# Codeshelf-0009_v03.net
KiCad netlist of a schematic drawn in EAGLE
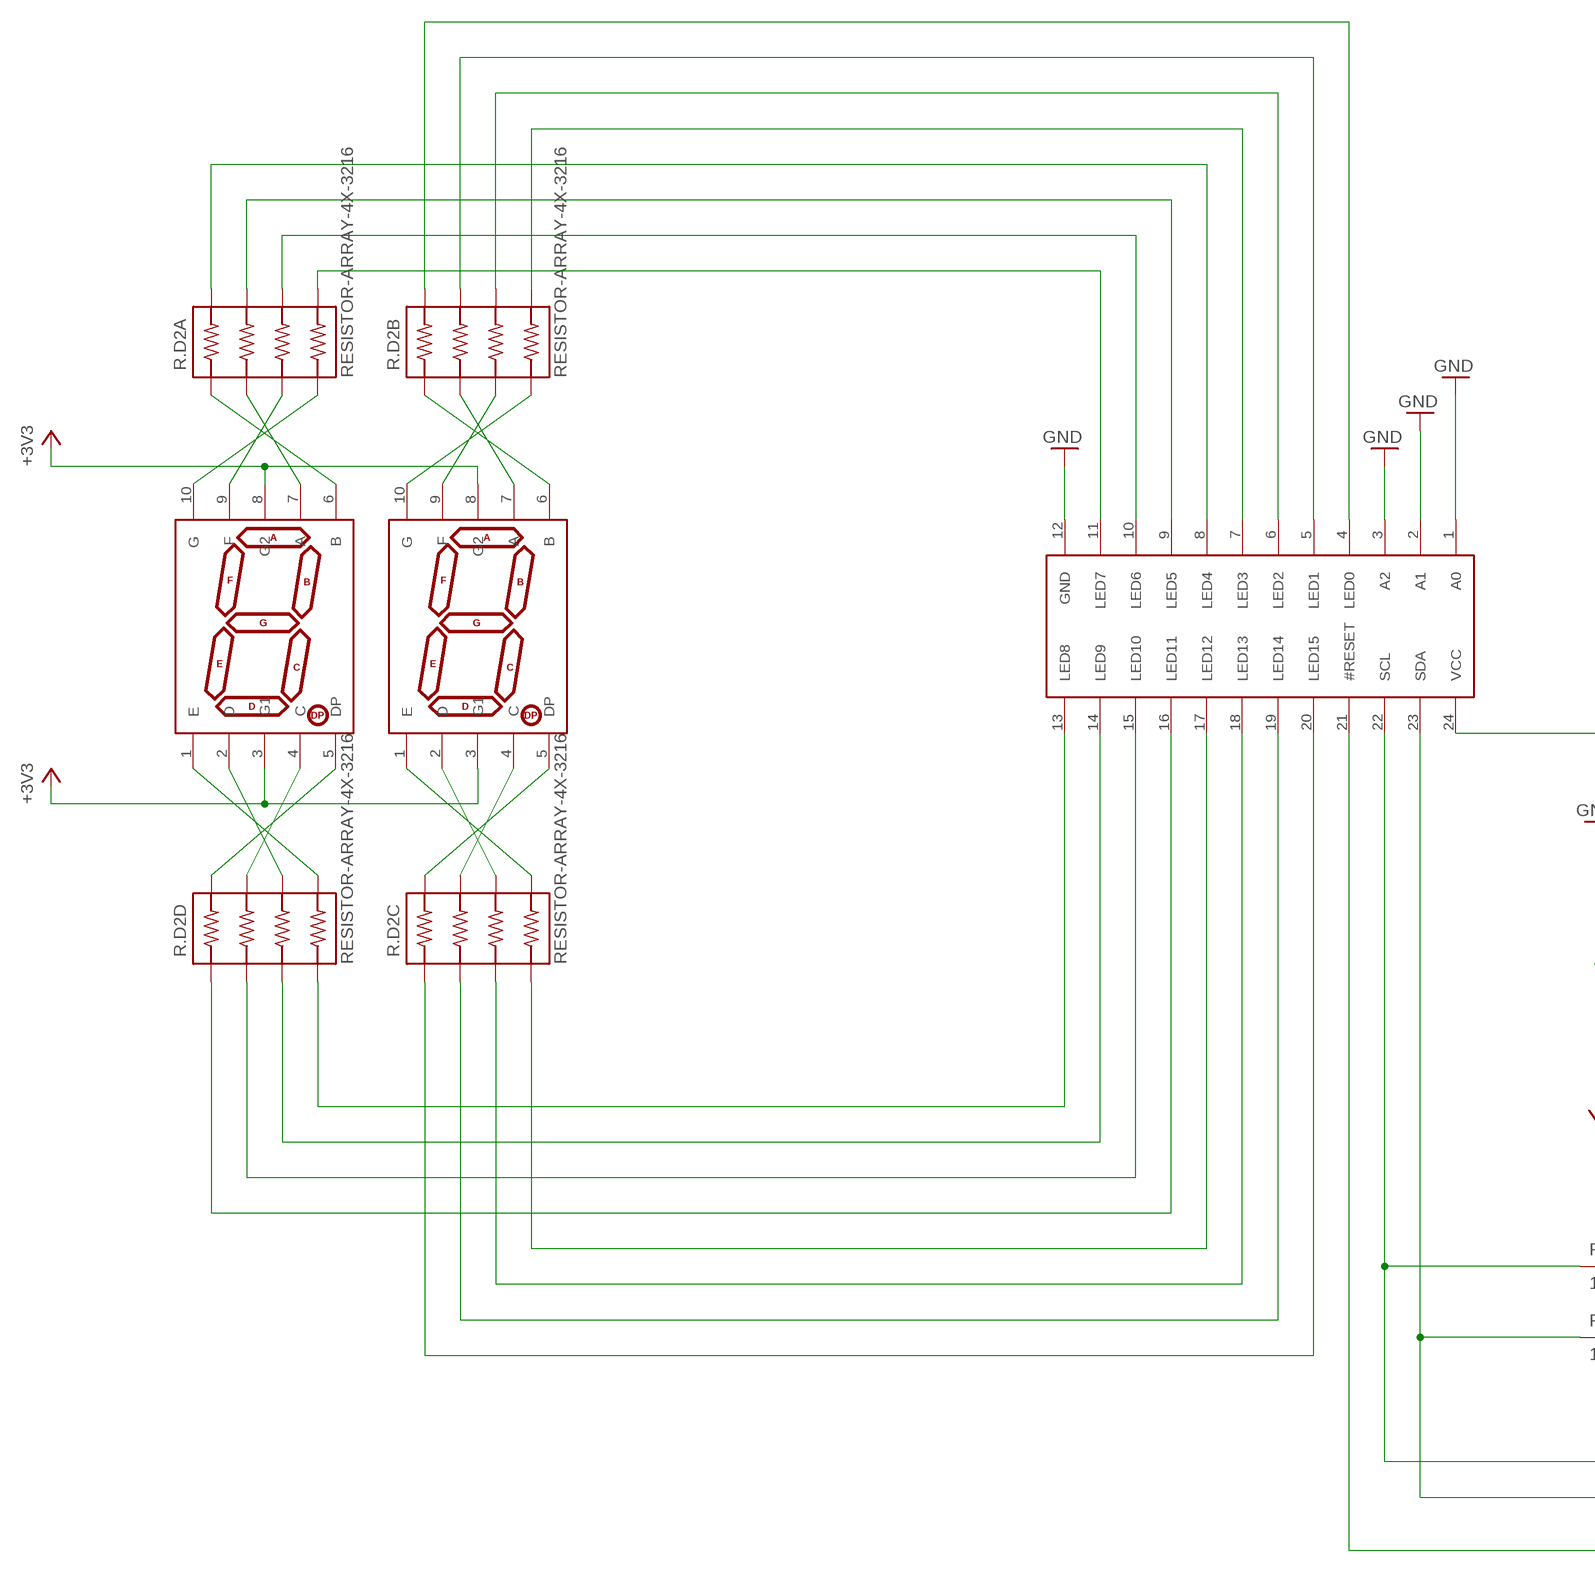
[diagram p0: schematic, sheet 1, part 1 of 2]
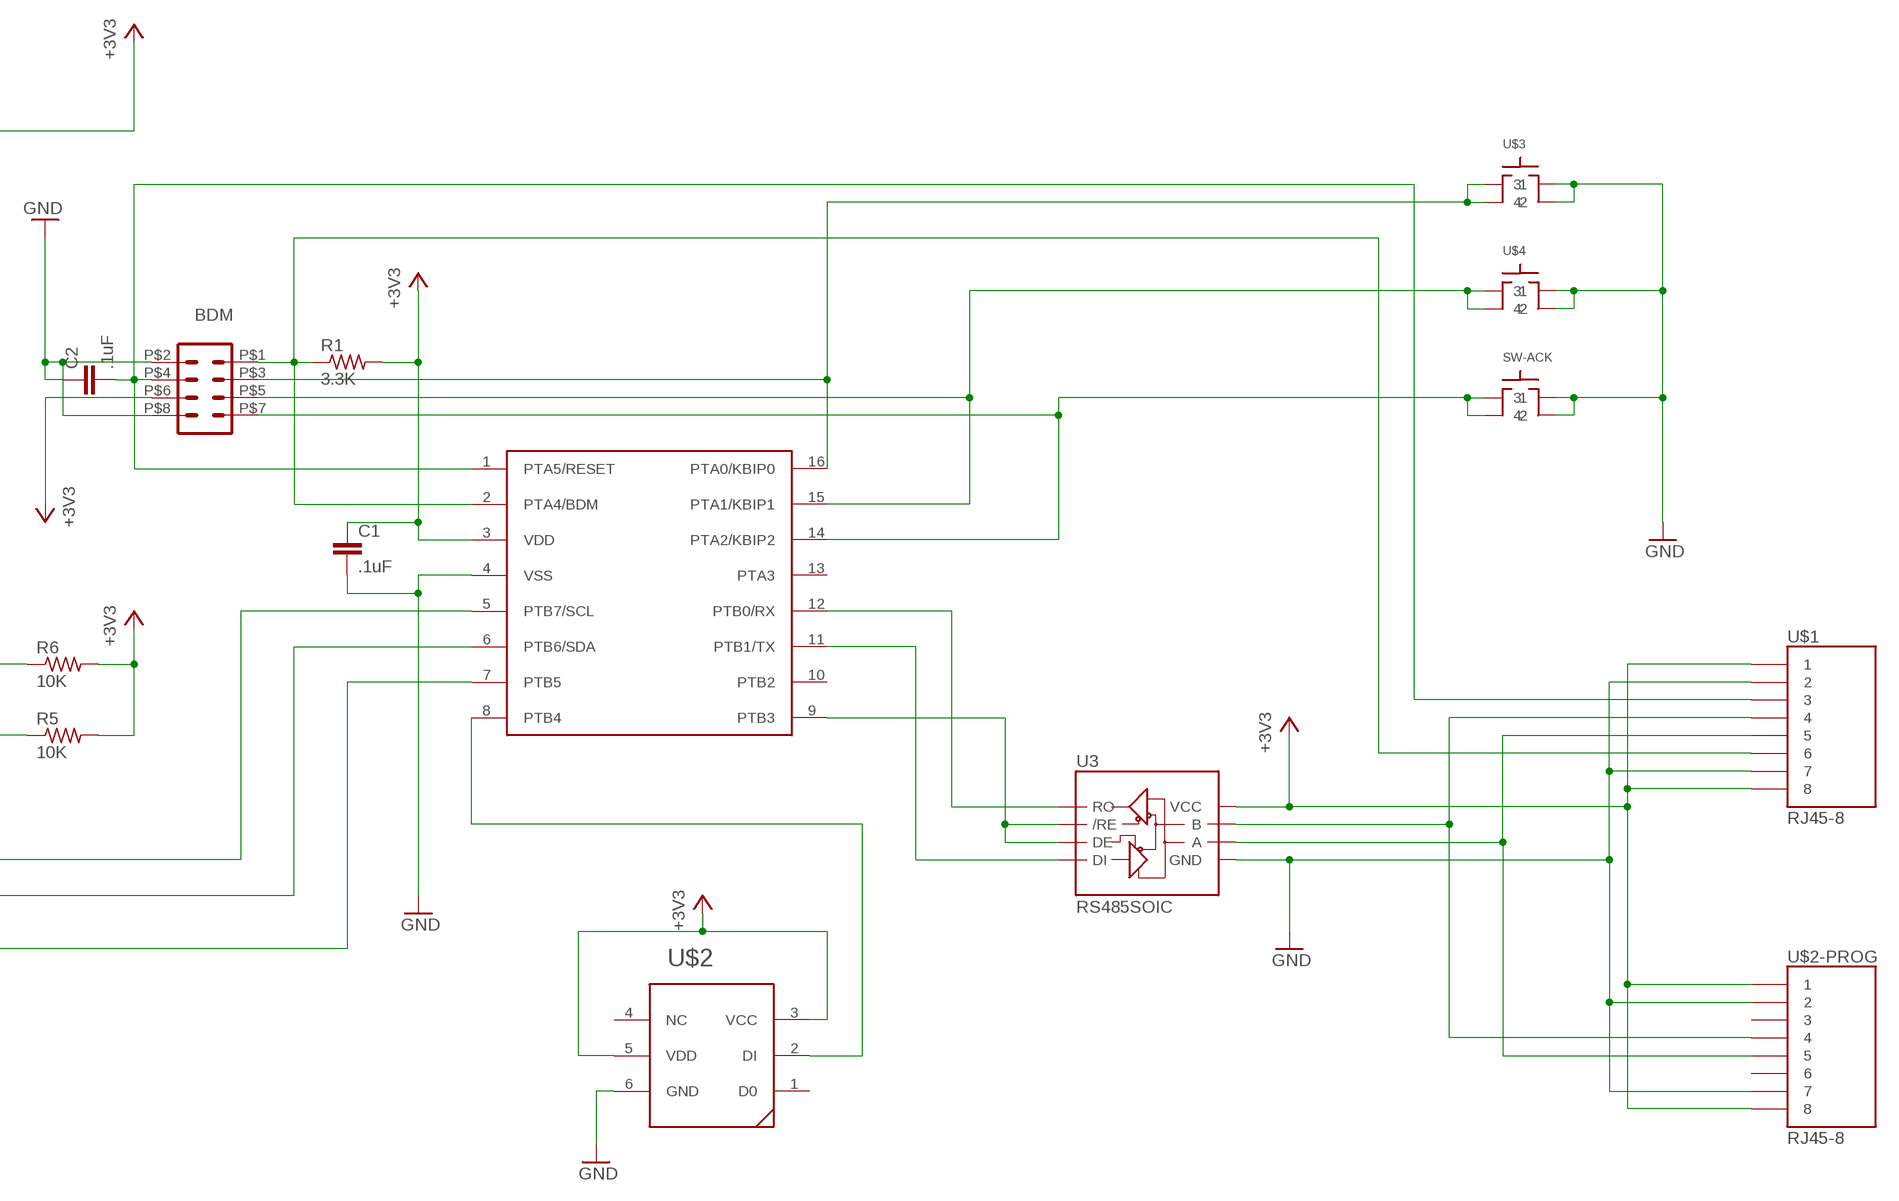
[diagram p1: schematic, sheet 1, part 2 of 2]

(export (version "E")
  (design (tool "Eeschema 10.0.6"))
  (components
    (comp (ref "BDM")
      (value "TP2X4SMD")
      (footprint "eagle-import:SMD4X2")
      (libsource (lib "eagle-import") (part "TP2X4SMD"))
    )
    (comp (ref "C1")
      (value ".1uF")
      (footprint "eagle-import:C0402")
      (libsource (lib "eagle-import") (part "RF-C0402"))
    )
    (comp (ref "C2")
      (value ".1uF")
      (footprint "eagle-import:C0402")
      (libsource (lib "eagle-import") (part "RF-C0402"))
    )
    (comp (ref "LED1")
      (value "7SEGMENT-1DIGITSMD")
      (footprint "eagle-import:7SEGMENT-1DIG-.40-SMD")
      (libsource (lib "eagle-import") (part "7SEGMENT-1DIGITSMD"))
    )
    (comp (ref "LED2")
      (value "7SEGMENT-1DIGITSMD")
      (footprint "eagle-import:7SEGMENT-1DIG-.40-SMD")
      (libsource (lib "eagle-import") (part "7SEGMENT-1DIGITSMD"))
    )
    (comp (ref "R.D2A")
      (value "RESISTOR-ARRAY-4X-3216")
      (footprint "eagle-import:3216-4X")
      (libsource (lib "eagle-import") (part "RESISTOR-ARRAY-4X-3216"))
    )
    (comp (ref "R.D2B")
      (value "RESISTOR-ARRAY-4X-3216")
      (footprint "eagle-import:3216-4X")
      (libsource (lib "eagle-import") (part "RESISTOR-ARRAY-4X-3216"))
    )
    (comp (ref "R.D2C")
      (value "RESISTOR-ARRAY-4X-3216")
      (footprint "eagle-import:3216-4X")
      (libsource (lib "eagle-import") (part "RESISTOR-ARRAY-4X-3216"))
    )
    (comp (ref "R.D2D")
      (value "RESISTOR-ARRAY-4X-3216")
      (footprint "eagle-import:3216-4X")
      (libsource (lib "eagle-import") (part "RESISTOR-ARRAY-4X-3216"))
    )
    (comp (ref "R1")
      (value "3.3K")
      (footprint "eagle-import:RF-R0402")
      (libsource (lib "eagle-import") (part "RF-R0402"))
    )
    (comp (ref "R5")
      (value "10K")
      (footprint "eagle-import:RF-R0402")
      (libsource (lib "eagle-import") (part "RF-R0402"))
    )
    (comp (ref "R6")
      (value "10K")
      (footprint "eagle-import:RF-R0402")
      (libsource (lib "eagle-import") (part "RF-R0402"))
    )
    (comp (ref "SW-ACK")
      (value "SWITCH-TACTILE-320.03E11")
      (footprint "eagle-import:SWITCH-TACTILE-320.03E11")
      (libsource (lib "eagle-import") (part "SWITCH-TACTILE-320.03E11"))
    )
    (comp (ref "U$1")
      (value "RJ45-8")
      (footprint "eagle-import:MOLEX-0955016649")
      (libsource (lib "eagle-import") (part "RJ45-8"))
    )
    (comp (ref "U$2")
      (value "WS2812")
      (footprint "eagle-import:PLCC-6")
      (libsource (lib "eagle-import") (part "WS2812"))
    )
    (comp (ref "U$2-PROG")
      (value "RJ45-8")
      (footprint "eagle-import:MOLEX-0955016649")
      (libsource (lib "eagle-import") (part "RJ45-8"))
    )
    (comp (ref "U$3")
      (value "SWITCH-TACTILE")
      (footprint "eagle-import:ESWITCH-TL3301PF")
      (libsource (lib "eagle-import") (part "SWITCH-TACTILE"))
    )
    (comp (ref "U$4")
      (value "SWITCH-TACTILE")
      (footprint "eagle-import:ESWITCH-TL3301PF")
      (libsource (lib "eagle-import") (part "SWITCH-TACTILE"))
    )
    (comp (ref "U1")
      (value "MC9S08QG-DT")
      (footprint "eagle-import:TSSOP16")
      (libsource (lib "eagle-import") (part "MC9S08QG-DT"))
    )
    (comp (ref "U3")
      (value "RS485SOIC")
      (footprint "eagle-import:SO08")
      (libsource (lib "eagle-import") (part "RS485SOIC"))
    )
    (comp (ref "U4")
      (value "CAT9552")
      (footprint "eagle-import:TSSOP24")
      (libsource (lib "eagle-import") (part "CAT9552"))
    )
  )
  (nets
    (net (code "1") (name "+3V3") (class "Default")
      (node (ref "BDM") (pin "P$6") (pinfunction "6_P$6") (pintype "passive"))
      (node (ref "C1") (pin "1") (pinfunction "1_1") (pintype "passive"))
      (node (ref "LED1") (pin "3") (pinfunction "G1_3") (pintype "bidirectional"))
      (node (ref "LED1") (pin "8") (pinfunction "G2_8") (pintype "bidirectional"))
      (node (ref "LED2") (pin "3") (pinfunction "G1_3") (pintype "bidirectional"))
      (node (ref "LED2") (pin "8") (pinfunction "G2_8") (pintype "bidirectional"))
      (node (ref "R1") (pin "2") (pinfunction "2_2") (pintype "passive"))
      (node (ref "R5") (pin "2") (pinfunction "2_2") (pintype "passive"))
      (node (ref "R6") (pin "2") (pinfunction "2_2") (pintype "passive"))
      (node (ref "U$1") (pin "P$1") (pinfunction "1_P$1") (pintype "bidirectional"))
      (node (ref "U$1") (pin "P$8") (pinfunction "8_P$8") (pintype "bidirectional"))
      (node (ref "U$2") (pin "3") (pinfunction "VCC_3") (pintype "bidirectional"))
      (node (ref "U$2") (pin "5") (pinfunction "VDD_5") (pintype "bidirectional"))
      (node (ref "U$2-PROG") (pin "P$1") (pinfunction "1_P$1") (pintype "bidirectional"))
      (node (ref "U$2-PROG") (pin "P$8") (pinfunction "8_P$8") (pintype "bidirectional"))
      (node (ref "U1") (pin "3") (pinfunction "VDD_3") (pintype "bidirectional"))
      (node (ref "U3") (pin "8") (pinfunction "VCC_8") (pintype "bidirectional"))
      (node (ref "U4") (pin "24") (pinfunction "VCC_24") (pintype "bidirectional"))
    )
    (net (code "2") (name "GND") (class "Default")
      (node (ref "BDM") (pin "P$2") (pinfunction "2_P$2") (pintype "passive"))
      (node (ref "BDM") (pin "P$8") (pinfunction "8_P$8") (pintype "passive"))
      (node (ref "C1") (pin "2") (pinfunction "2_2") (pintype "passive"))
      (node (ref "C2") (pin "1") (pinfunction "1_1") (pintype "passive"))
      (node (ref "SW-ACK") (pin "P$3") (pinfunction "3_P$3") (pintype "input"))
      (node (ref "SW-ACK") (pin "P$4") (pinfunction "4_P$4") (pintype "input"))
      (node (ref "U$1") (pin "P$2") (pinfunction "2_P$2") (pintype "bidirectional"))
      (node (ref "U$1") (pin "P$7") (pinfunction "7_P$7") (pintype "bidirectional"))
      (node (ref "U$2") (pin "6") (pinfunction "GND_6") (pintype "bidirectional"))
      (node (ref "U$2-PROG") (pin "P$2") (pinfunction "2_P$2") (pintype "bidirectional"))
      (node (ref "U$2-PROG") (pin "P$7") (pinfunction "7_P$7") (pintype "bidirectional"))
      (node (ref "U$3") (pin "3") (pinfunction "3_3") (pintype "input"))
      (node (ref "U$3") (pin "4") (pinfunction "4_4") (pintype "input"))
      (node (ref "U$4") (pin "3") (pinfunction "3_3") (pintype "input"))
      (node (ref "U$4") (pin "4") (pinfunction "4_4") (pintype "input"))
      (node (ref "U1") (pin "4") (pinfunction "VSS_4") (pintype "bidirectional"))
      (node (ref "U3") (pin "5") (pinfunction "GND_5") (pintype "bidirectional"))
      (node (ref "U4") (pin "1") (pinfunction "A0_1") (pintype "bidirectional"))
      (node (ref "U4") (pin "12") (pinfunction "GND_12") (pintype "bidirectional"))
      (node (ref "U4") (pin "2") (pinfunction "A1_2") (pintype "bidirectional"))
      (node (ref "U4") (pin "3") (pinfunction "A2_3") (pintype "bidirectional"))
    )
    (net (code "3") (name "Net-(BDM-1)") (class "Default")
      (node (ref "BDM") (pin "P$1") (pinfunction "1_P$1") (pintype "passive"))
      (node (ref "R1") (pin "1") (pinfunction "1_1") (pintype "passive"))
      (node (ref "U$1") (pin "P$6") (pinfunction "6_P$6") (pintype "bidirectional"))
      (node (ref "U1") (pin "2") (pinfunction "PTA4/BDM_2") (pintype "bidirectional"))
    )
    (net (code "4") (name "Net-(BDM-3)") (class "Default")
      (node (ref "BDM") (pin "P$3") (pinfunction "3_P$3") (pintype "passive"))
      (node (ref "U$3") (pin "1") (pinfunction "1_1") (pintype "input"))
      (node (ref "U$3") (pin "2") (pinfunction "2_2") (pintype "input"))
      (node (ref "U1") (pin "16") (pinfunction "PTA0/KBIP0_16") (pintype "bidirectional"))
    )
    (net (code "5") (name "Net-(BDM-4)") (class "Default")
      (node (ref "BDM") (pin "P$4") (pinfunction "4_P$4") (pintype "passive"))
      (node (ref "C2") (pin "2") (pinfunction "2_2") (pintype "passive"))
      (node (ref "U$1") (pin "P$3") (pinfunction "3_P$3") (pintype "bidirectional"))
      (node (ref "U1") (pin "1") (pinfunction "PTA5/RESET_1") (pintype "bidirectional"))
    )
    (net (code "6") (name "Net-(BDM-5)") (class "Default")
      (node (ref "BDM") (pin "P$5") (pinfunction "5_P$5") (pintype "passive"))
      (node (ref "U$4") (pin "1") (pinfunction "1_1") (pintype "input"))
      (node (ref "U$4") (pin "2") (pinfunction "2_2") (pintype "input"))
      (node (ref "U1") (pin "15") (pinfunction "PTA1/KBIP1_15") (pintype "bidirectional"))
    )
    (net (code "7") (name "Net-(BDM-7)") (class "Default")
      (node (ref "BDM") (pin "P$7") (pinfunction "7_P$7") (pintype "passive"))
      (node (ref "SW-ACK") (pin "P$1") (pinfunction "1_P$1") (pintype "input"))
      (node (ref "SW-ACK") (pin "P$2") (pinfunction "2_P$2") (pintype "input"))
      (node (ref "U1") (pin "14") (pinfunction "PTA2/KBIP2_14") (pintype "bidirectional"))
    )
    (net (code "8") (name "Net-(LED1-A)") (class "Default")
      (node (ref "LED1") (pin "7") (pinfunction "A_7") (pintype "bidirectional"))
      (node (ref "R.D2B") (pin "2") (pinfunction "2A_2") (pintype "passive"))
    )
    (net (code "9") (name "Net-(LED1-B)") (class "Default")
      (node (ref "LED1") (pin "6") (pinfunction "B_6") (pintype "bidirectional"))
      (node (ref "R.D2B") (pin "1") (pinfunction "1A_1") (pintype "passive"))
    )
    (net (code "10") (name "Net-(LED1-C)") (class "Default")
      (node (ref "LED1") (pin "4") (pinfunction "C_4") (pintype "bidirectional"))
      (node (ref "R.D2C") (pin "7") (pinfunction "2B_7") (pintype "passive"))
    )
    (net (code "11") (name "Net-(LED1-D)") (class "Default")
      (node (ref "LED1") (pin "2") (pinfunction "D_2") (pintype "bidirectional"))
      (node (ref "R.D2C") (pin "6") (pinfunction "3B_6") (pintype "passive"))
    )
    (net (code "12") (name "Net-(LED1-DP)") (class "Default")
      (node (ref "LED1") (pin "5") (pinfunction "DP_5") (pintype "bidirectional"))
      (node (ref "R.D2C") (pin "8") (pinfunction "1B_8") (pintype "passive"))
    )
    (net (code "13") (name "Net-(LED1-E)") (class "Default")
      (node (ref "LED1") (pin "1") (pinfunction "E_1") (pintype "bidirectional"))
      (node (ref "R.D2C") (pin "5") (pinfunction "4B_5") (pintype "passive"))
    )
    (net (code "14") (name "Net-(LED1-F)") (class "Default")
      (node (ref "LED1") (pin "9") (pinfunction "F_9") (pintype "bidirectional"))
      (node (ref "R.D2B") (pin "3") (pinfunction "3A_3") (pintype "passive"))
    )
    (net (code "15") (name "Net-(LED1-G)") (class "Default")
      (node (ref "LED1") (pin "10") (pinfunction "G_10") (pintype "bidirectional"))
      (node (ref "R.D2B") (pin "4") (pinfunction "4A_4") (pintype "passive"))
    )
    (net (code "16") (name "Net-(LED2-A)") (class "Default")
      (node (ref "LED2") (pin "7") (pinfunction "A_7") (pintype "bidirectional"))
      (node (ref "R.D2A") (pin "2") (pinfunction "2A_2") (pintype "passive"))
    )
    (net (code "17") (name "Net-(LED2-B)") (class "Default")
      (node (ref "LED2") (pin "6") (pinfunction "B_6") (pintype "bidirectional"))
      (node (ref "R.D2A") (pin "1") (pinfunction "1A_1") (pintype "passive"))
    )
    (net (code "18") (name "Net-(LED2-C)") (class "Default")
      (node (ref "LED2") (pin "4") (pinfunction "C_4") (pintype "bidirectional"))
      (node (ref "R.D2D") (pin "7") (pinfunction "2B_7") (pintype "passive"))
    )
    (net (code "19") (name "Net-(LED2-D)") (class "Default")
      (node (ref "LED2") (pin "2") (pinfunction "D_2") (pintype "bidirectional"))
      (node (ref "R.D2D") (pin "6") (pinfunction "3B_6") (pintype "passive"))
    )
    (net (code "20") (name "Net-(LED2-DP)") (class "Default")
      (node (ref "LED2") (pin "5") (pinfunction "DP_5") (pintype "bidirectional"))
      (node (ref "R.D2D") (pin "8") (pinfunction "1B_8") (pintype "passive"))
    )
    (net (code "21") (name "Net-(LED2-E)") (class "Default")
      (node (ref "LED2") (pin "1") (pinfunction "E_1") (pintype "bidirectional"))
      (node (ref "R.D2D") (pin "5") (pinfunction "4B_5") (pintype "passive"))
    )
    (net (code "22") (name "Net-(LED2-F)") (class "Default")
      (node (ref "LED2") (pin "9") (pinfunction "F_9") (pintype "bidirectional"))
      (node (ref "R.D2A") (pin "3") (pinfunction "3A_3") (pintype "passive"))
    )
    (net (code "23") (name "Net-(LED2-G)") (class "Default")
      (node (ref "LED2") (pin "10") (pinfunction "G_10") (pintype "bidirectional"))
      (node (ref "R.D2A") (pin "4") (pinfunction "4A_4") (pintype "passive"))
    )
    (net (code "24") (name "Net-(R.D2A-1B)") (class "Default")
      (node (ref "R.D2A") (pin "8") (pinfunction "1B_8") (pintype "passive"))
      (node (ref "U4") (pin "8") (pinfunction "LED4_8") (pintype "bidirectional"))
    )
    (net (code "25") (name "Net-(R.D2A-2B)") (class "Default")
      (node (ref "R.D2A") (pin "7") (pinfunction "2B_7") (pintype "passive"))
      (node (ref "U4") (pin "9") (pinfunction "LED5_9") (pintype "bidirectional"))
    )
    (net (code "26") (name "Net-(R.D2A-3B)") (class "Default")
      (node (ref "R.D2A") (pin "6") (pinfunction "3B_6") (pintype "passive"))
      (node (ref "U4") (pin "10") (pinfunction "LED6_10") (pintype "bidirectional"))
    )
    (net (code "27") (name "Net-(R.D2A-4B)") (class "Default")
      (node (ref "R.D2A") (pin "5") (pinfunction "4B_5") (pintype "passive"))
      (node (ref "U4") (pin "11") (pinfunction "LED7_11") (pintype "bidirectional"))
    )
    (net (code "28") (name "Net-(R.D2B-1B)") (class "Default")
      (node (ref "R.D2B") (pin "8") (pinfunction "1B_8") (pintype "passive"))
      (node (ref "U4") (pin "4") (pinfunction "LED0_4") (pintype "bidirectional"))
    )
    (net (code "29") (name "Net-(R.D2B-2B)") (class "Default")
      (node (ref "R.D2B") (pin "7") (pinfunction "2B_7") (pintype "passive"))
      (node (ref "U4") (pin "5") (pinfunction "LED1_5") (pintype "bidirectional"))
    )
    (net (code "30") (name "Net-(R.D2B-3B)") (class "Default")
      (node (ref "R.D2B") (pin "6") (pinfunction "3B_6") (pintype "passive"))
      (node (ref "U4") (pin "6") (pinfunction "LED2_6") (pintype "bidirectional"))
    )
    (net (code "31") (name "Net-(R.D2B-4B)") (class "Default")
      (node (ref "R.D2B") (pin "5") (pinfunction "4B_5") (pintype "passive"))
      (node (ref "U4") (pin "7") (pinfunction "LED3_7") (pintype "bidirectional"))
    )
    (net (code "32") (name "Net-(R.D2C-1A)") (class "Default")
      (node (ref "R.D2C") (pin "1") (pinfunction "1A_1") (pintype "passive"))
      (node (ref "U4") (pin "20") (pinfunction "LED15_20") (pintype "bidirectional"))
    )
    (net (code "33") (name "Net-(R.D2C-2A)") (class "Default")
      (node (ref "R.D2C") (pin "2") (pinfunction "2A_2") (pintype "passive"))
      (node (ref "U4") (pin "19") (pinfunction "LED14_19") (pintype "bidirectional"))
    )
    (net (code "34") (name "Net-(R.D2C-3A)") (class "Default")
      (node (ref "R.D2C") (pin "3") (pinfunction "3A_3") (pintype "passive"))
      (node (ref "U4") (pin "18") (pinfunction "LED13_18") (pintype "bidirectional"))
    )
    (net (code "35") (name "Net-(R.D2C-4A)") (class "Default")
      (node (ref "R.D2C") (pin "4") (pinfunction "4A_4") (pintype "passive"))
      (node (ref "U4") (pin "17") (pinfunction "LED12_17") (pintype "bidirectional"))
    )
    (net (code "36") (name "Net-(R.D2D-1A)") (class "Default")
      (node (ref "R.D2D") (pin "1") (pinfunction "1A_1") (pintype "passive"))
      (node (ref "U4") (pin "16") (pinfunction "LED11_16") (pintype "bidirectional"))
    )
    (net (code "37") (name "Net-(R.D2D-2A)") (class "Default")
      (node (ref "R.D2D") (pin "2") (pinfunction "2A_2") (pintype "passive"))
      (node (ref "U4") (pin "15") (pinfunction "LED10_15") (pintype "bidirectional"))
    )
    (net (code "38") (name "Net-(R.D2D-3A)") (class "Default")
      (node (ref "R.D2D") (pin "3") (pinfunction "3A_3") (pintype "passive"))
      (node (ref "U4") (pin "14") (pinfunction "LED9_14") (pintype "bidirectional"))
    )
    (net (code "39") (name "Net-(R.D2D-4A)") (class "Default")
      (node (ref "R.D2D") (pin "4") (pinfunction "4A_4") (pintype "passive"))
      (node (ref "U4") (pin "13") (pinfunction "LED8_13") (pintype "bidirectional"))
    )
    (net (code "40") (name "Net-(U$1-4)") (class "Default")
      (node (ref "U$1") (pin "P$4") (pinfunction "4_P$4") (pintype "bidirectional"))
      (node (ref "U$2-PROG") (pin "P$4") (pinfunction "4_P$4") (pintype "bidirectional"))
      (node (ref "U3") (pin "7") (pinfunction "B_7") (pintype "bidirectional"))
    )
    (net (code "41") (name "Net-(U$1-5)") (class "Default")
      (node (ref "U$1") (pin "P$5") (pinfunction "5_P$5") (pintype "bidirectional"))
      (node (ref "U$2-PROG") (pin "P$5") (pinfunction "5_P$5") (pintype "bidirectional"))
      (node (ref "U3") (pin "6") (pinfunction "A_6") (pintype "bidirectional"))
    )
    (net (code "42") (name "Net-(U$2-DI)") (class "Default")
      (node (ref "U$2") (pin "2") (pinfunction "DI_2") (pintype "bidirectional"))
      (node (ref "U1") (pin "8") (pinfunction "PTB4_8") (pintype "bidirectional"))
    )
    (net (code "43") (name "Net-(U1-PTB0{slash}RX)") (class "Default")
      (node (ref "U1") (pin "12") (pinfunction "PTB0/RX_12") (pintype "bidirectional"))
      (node (ref "U3") (pin "1") (pinfunction "RO_1") (pintype "bidirectional"))
    )
    (net (code "44") (name "Net-(U1-PTB1{slash}TX)") (class "Default")
      (node (ref "U1") (pin "11") (pinfunction "PTB1/TX_11") (pintype "bidirectional"))
      (node (ref "U3") (pin "4") (pinfunction "DI_4") (pintype "bidirectional"))
    )
    (net (code "45") (name "Net-(U1-PTB3)") (class "Default")
      (node (ref "U1") (pin "9") (pinfunction "PTB3_9") (pintype "bidirectional"))
      (node (ref "U3") (pin "2") (pinfunction "/RE_2") (pintype "bidirectional"))
      (node (ref "U3") (pin "3") (pinfunction "DE_3") (pintype "bidirectional"))
    )
    (net (code "46") (name "Net-(U1-PTB5)") (class "Default")
      (node (ref "U1") (pin "7") (pinfunction "PTB5_7") (pintype "bidirectional"))
      (node (ref "U4") (pin "21") (pinfunction "#RESET_21") (pintype "bidirectional"))
    )
    (net (code "47") (name "Net-(U1-PTB6{slash}SDA)") (class "Default")
      (node (ref "R5") (pin "1") (pinfunction "1_1") (pintype "passive"))
      (node (ref "U1") (pin "6") (pinfunction "PTB6/SDA_6") (pintype "bidirectional"))
      (node (ref "U4") (pin "23") (pinfunction "SDA_23") (pintype "bidirectional"))
    )
    (net (code "48") (name "Net-(U1-PTB7{slash}SCL)") (class "Default")
      (node (ref "R6") (pin "1") (pinfunction "1_1") (pintype "passive"))
      (node (ref "U1") (pin "5") (pinfunction "PTB7/SCL_5") (pintype "bidirectional"))
      (node (ref "U4") (pin "22") (pinfunction "SCL_22") (pintype "bidirectional"))
    )
    (net (code "49") (name "unconnected-(U$2-D0-Pad1)") (class "Default")
      (node (ref "U$2") (pin "1") (pinfunction "D0_1") (pintype "bidirectional"))
    )
    (net (code "50") (name "unconnected-(U$2-NC-Pad4)") (class "Default")
      (node (ref "U$2") (pin "4") (pinfunction "NC_4") (pintype "bidirectional"))
    )
    (net (code "51") (name "unconnected-(U$2-PROG-3-PadP$3)") (class "Default")
      (node (ref "U$2-PROG") (pin "P$3") (pinfunction "3_P$3") (pintype "bidirectional"))
    )
    (net (code "52") (name "unconnected-(U$2-PROG-6-PadP$6)") (class "Default")
      (node (ref "U$2-PROG") (pin "P$6") (pinfunction "6_P$6") (pintype "bidirectional"))
    )
    (net (code "53") (name "unconnected-(U1-PTA3-Pad13)") (class "Default")
      (node (ref "U1") (pin "13") (pinfunction "PTA3_13") (pintype "bidirectional"))
    )
    (net (code "54") (name "unconnected-(U1-PTB2-Pad10)") (class "Default")
      (node (ref "U1") (pin "10") (pinfunction "PTB2_10") (pintype "bidirectional"))
    )
  )
)
